# FF.net
KiCad netlist of a schematic drawn in Altium Designer
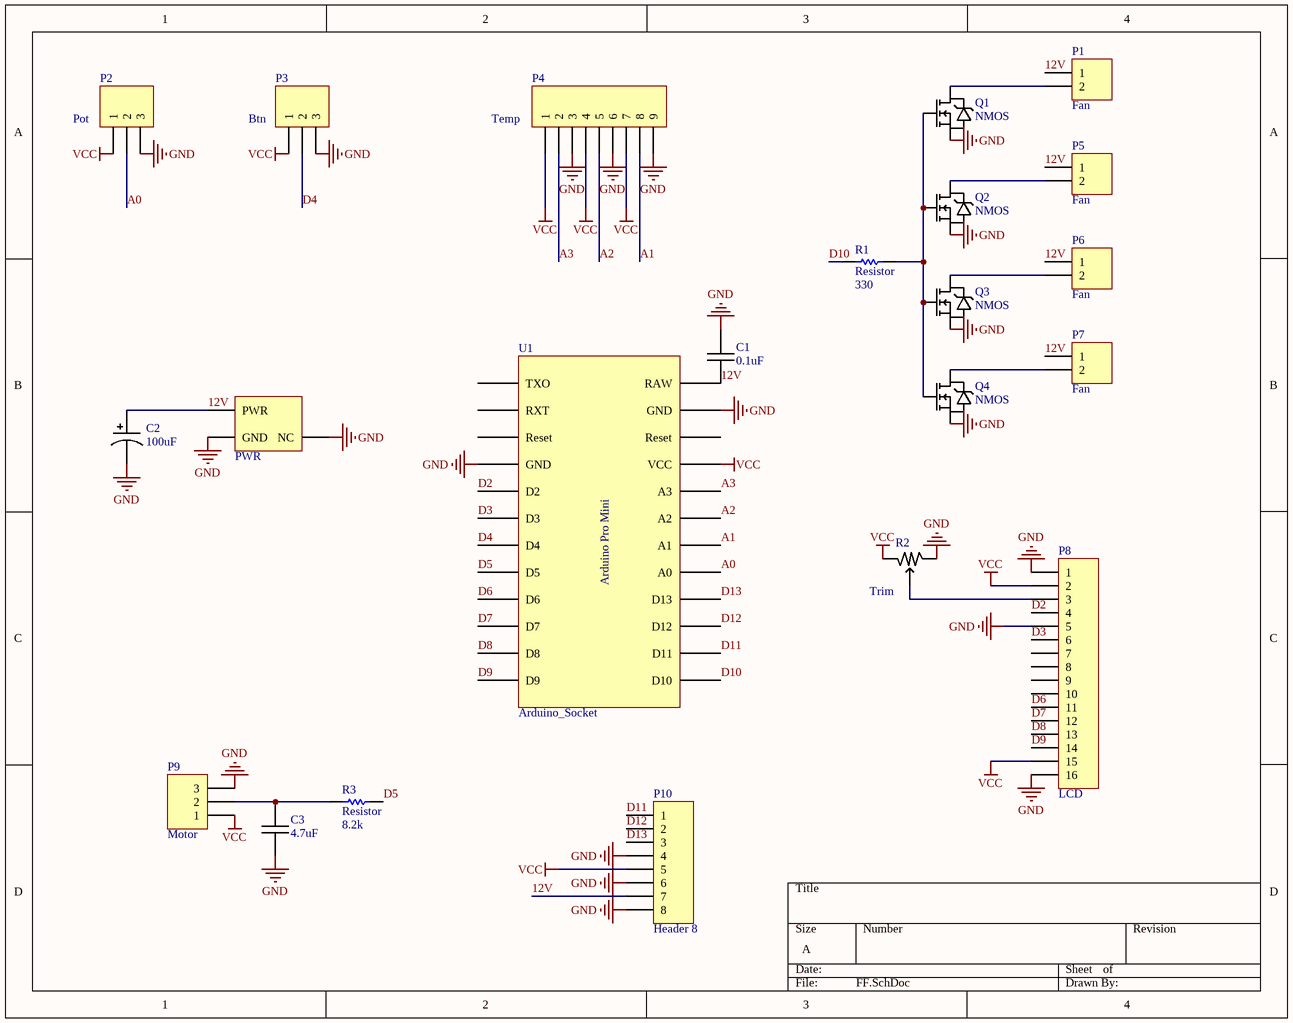
[diagram p0: FF.SchDoc]

(export (version "E")
  (design (tool "Eeschema 10.0.6"))
  (components
    (comp (ref "C1")
      (value "Capacitor")
      (footprint "Cap Axial")
      (description "Ceramic Capacitor")
      (fields (field (name "ALTIUM_UNNAMED_1") "0.1uF"))
      (libsource (lib "Wampler_Devices") (part "Capacitor"))
    )
    (comp (ref "C2")
      (value "Capacitor")
      (footprint "Cap Radial-Can 200")
      (description "Electrolytic Capacitor")
      (fields (field (name "ALTIUM_UNNAMED_1") "100uF"))
      (libsource (lib "Wampler_Devices") (part "Capacitor Polar"))
    )
    (comp (ref "C3")
      (value "Capacitor")
      (footprint "Cap Axial")
      (description "Ceramic Capacitor")
      (fields (field (name "ALTIUM_UNNAMED_1") "4.7uF"))
      (libsource (lib "Wampler_Devices") (part "Capacitor"))
    )
    (comp (ref "P1")
      (value "Fan")
      (footprint "HDR1X2")
      (description "Header, 2-Pin")
      (fields (field (name "PUBLISHER") "Altium Limited"))
      (libsource (lib "Miscellaneous Connectors") (part "Header 2"))
    )
    (comp (ref "P2")
      (value "Pot")
      (footprint "HDR1X3")
      (description "Header, 3-Pin")
      (fields (field (name "PUBLISHER") "Altium Limited"))
      (libsource (lib "") (part "Header 3_1"))
    )
    (comp (ref "P3")
      (value "Btn")
      (footprint "HDR1X3")
      (description "Header, 3-Pin")
      (fields (field (name "PUBLISHER") "Altium Limited"))
      (libsource (lib "") (part "Header 3_1"))
    )
    (comp (ref "P4")
      (value "Temp")
      (footprint "HDR1X9")
      (description "Header, 9-Pin")
      (fields (field (name "PUBLISHER") "Altium Limited"))
      (libsource (lib "Miscellaneous Connectors") (part "Header 9"))
    )
    (comp (ref "P5")
      (value "Fan")
      (footprint "HDR1X2")
      (description "Header, 2-Pin")
      (fields (field (name "PUBLISHER") "Altium Limited"))
      (libsource (lib "Miscellaneous Connectors") (part "Header 2"))
    )
    (comp (ref "P6")
      (value "Fan")
      (footprint "HDR1X2")
      (description "Header, 2-Pin")
      (fields (field (name "PUBLISHER") "Altium Limited"))
      (libsource (lib "Miscellaneous Connectors") (part "Header 2"))
    )
    (comp (ref "P7")
      (value "Fan")
      (footprint "HDR1X2")
      (description "Header, 2-Pin")
      (fields (field (name "PUBLISHER") "Altium Limited"))
      (libsource (lib "Miscellaneous Connectors") (part "Header 2"))
    )
    (comp (ref "P8")
      (value "LCD")
      (footprint "HDR1X16")
      (description "Header, 16-Pin")
      (fields (field (name "PUBLISHER") "Altium Limited"))
      (libsource (lib "Miscellaneous Connectors") (part "Header 16"))
    )
    (comp (ref "P9")
      (value "Motor")
      (footprint "HDR1X3")
      (description "Header, 3-Pin")
      (fields (field (name "PUBLISHER") "Altium Limited"))
      (libsource (lib "Miscellaneous Connectors") (part "Header 3"))
    )
    (comp (ref "P10")
      (value "Header 8")
      (footprint "HDR1X8")
      (description "Header, 8-Pin")
      (fields (field (name "PUBLISHER") "Altium Limited"))
      (libsource (lib "Miscellaneous Connectors") (part "Header 8"))
    )
    (comp (ref "PWR")
      (value "3.5mm Power Jack")
      (footprint "3.5mm Power Jack")
      (libsource (lib "Wampler_Connectors") (part "3.5mm Power Jack"))
    )
    (comp (ref "Q1") (value "NMOS") (footprint "TO-220") (libsource (lib "Wampler_Devices") (part "NMOS")))
    (comp (ref "Q2") (value "NMOS") (footprint "TO-220") (libsource (lib "Wampler_Devices") (part "NMOS")))
    (comp (ref "Q3") (value "NMOS") (footprint "TO-220") (libsource (lib "Wampler_Devices") (part "NMOS")))
    (comp (ref "Q4") (value "NMOS") (footprint "TO-220") (libsource (lib "Wampler_Devices") (part "NMOS")))
    (comp (ref "R1")
      (value "Resistor")
      (footprint "Res Axial 1/2W")
      (fields (field (name "ALTIUM_VALUE") "330") (field (name "PUBLISHER") "Altium Limited"))
      (libsource (lib "Wampler_Devices") (part "Resistor"))
    )
    (comp (ref "R2")
      (value "Trimmer Pot")
      (footprint "T73YP103KT20")
      (fields (field (name "ALTIUM_UNNAMED_1") "Trim"))
      (libsource (lib "Wampler_Devices") (part "Trimmer Pot"))
    )
    (comp (ref "R3")
      (value "Resistor")
      (footprint "Res Axial 1/2W")
      (fields (field (name "ALTIUM_VALUE") "8.2k") (field (name "PUBLISHER") "Altium Limited"))
      (libsource (lib "Wampler_Devices") (part "Resistor"))
    )
    (comp (ref "U1")
      (value "Arduino_Socket")
      (footprint "Arduino_Socket")
      (libsource (lib "Wampler_Devices") (part "Arduino_Socket"))
    )
  )
  (nets
    (net (code "1") (name "/12V") (class "Default")
      (node (ref "C1") (pin "0") (pinfunction "0_0") (pintype "passive"))
      (node (ref "C2") (pin "0") (pinfunction "0_0") (pintype "passive"))
      (node (ref "P1") (pin "1") (pinfunction "1_1") (pintype "passive"))
      (node (ref "P10") (pin "7") (pinfunction "7_7") (pintype "passive"))
      (node (ref "P5") (pin "1") (pinfunction "1_1") (pintype "passive"))
      (node (ref "P6") (pin "1") (pinfunction "1_1") (pintype "passive"))
      (node (ref "P7") (pin "1") (pinfunction "1_1") (pintype "passive"))
      (node (ref "PWR") (pin "1") (pinfunction "PWR_1") (pintype "passive"))
      (node (ref "U1") (pin "24") (pinfunction "RAW_24") (pintype "passive"))
    )
    (net (code "2") (name "/A0") (class "Default")
      (node (ref "P2") (pin "2") (pinfunction "2_2") (pintype "passive"))
      (node (ref "U1") (pin "17") (pinfunction "A0_17") (pintype "passive"))
    )
    (net (code "3") (name "/A1") (class "Default")
      (node (ref "P4") (pin "8") (pinfunction "8_8") (pintype "passive"))
      (node (ref "U1") (pin "18") (pinfunction "A1_18") (pintype "passive"))
    )
    (net (code "4") (name "/A2") (class "Default")
      (node (ref "P4") (pin "5") (pinfunction "5_5") (pintype "passive"))
      (node (ref "U1") (pin "19") (pinfunction "A2_19") (pintype "passive"))
    )
    (net (code "5") (name "/A3") (class "Default")
      (node (ref "P4") (pin "2") (pinfunction "2_2") (pintype "passive"))
      (node (ref "U1") (pin "20") (pinfunction "A3_20") (pintype "passive"))
    )
    (net (code "6") (name "/D2") (class "Default")
      (node (ref "P8") (pin "4") (pinfunction "4_4") (pintype "passive"))
      (node (ref "U1") (pin "5") (pinfunction "D2_5") (pintype "passive"))
    )
    (net (code "7") (name "/D3") (class "Default")
      (node (ref "P8") (pin "6") (pinfunction "6_6") (pintype "passive"))
      (node (ref "U1") (pin "6") (pinfunction "D3_6") (pintype "passive"))
    )
    (net (code "8") (name "/D4") (class "Default")
      (node (ref "P3") (pin "2") (pinfunction "2_2") (pintype "passive"))
      (node (ref "U1") (pin "7") (pinfunction "D4_7") (pintype "passive"))
    )
    (net (code "9") (name "/D5") (class "Default")
      (node (ref "R3") (pin "1") (pinfunction "1_1") (pintype "passive"))
      (node (ref "U1") (pin "8") (pinfunction "D5_8") (pintype "passive"))
    )
    (net (code "10") (name "/D6") (class "Default")
      (node (ref "P8") (pin "11") (pinfunction "11_11") (pintype "passive"))
      (node (ref "U1") (pin "9") (pinfunction "D6_9") (pintype "passive"))
    )
    (net (code "11") (name "/D7") (class "Default")
      (node (ref "P8") (pin "12") (pinfunction "12_12") (pintype "passive"))
      (node (ref "U1") (pin "10") (pinfunction "D7_10") (pintype "passive"))
    )
    (net (code "12") (name "/D8") (class "Default")
      (node (ref "P8") (pin "13") (pinfunction "13_13") (pintype "passive"))
      (node (ref "U1") (pin "11") (pinfunction "D8_11") (pintype "passive"))
    )
    (net (code "13") (name "/D9") (class "Default")
      (node (ref "P8") (pin "14") (pinfunction "14_14") (pintype "passive"))
      (node (ref "U1") (pin "12") (pinfunction "D9_12") (pintype "passive"))
    )
    (net (code "14") (name "/D10") (class "Default")
      (node (ref "R1") (pin "1") (pinfunction "1_1") (pintype "passive"))
      (node (ref "U1") (pin "13") (pinfunction "D10_13") (pintype "passive"))
    )
    (net (code "15") (name "/D11") (class "Default")
      (node (ref "P10") (pin "1") (pinfunction "1_1") (pintype "passive"))
      (node (ref "U1") (pin "14") (pinfunction "D11_14") (pintype "passive"))
    )
    (net (code "16") (name "/D12") (class "Default")
      (node (ref "P10") (pin "2") (pinfunction "2_2") (pintype "passive"))
      (node (ref "U1") (pin "15") (pinfunction "D12_15") (pintype "passive"))
    )
    (net (code "17") (name "/D13") (class "Default")
      (node (ref "P10") (pin "3") (pinfunction "3_3") (pintype "passive"))
      (node (ref "U1") (pin "16") (pinfunction "D13_16") (pintype "passive"))
    )
    (net (code "18") (name "GND") (class "Default")
      (node (ref "C1") (pin "1") (pinfunction "1_1") (pintype "passive"))
      (node (ref "C2") (pin "1") (pinfunction "1_1") (pintype "passive"))
      (node (ref "C3") (pin "0") (pinfunction "0_0") (pintype "passive"))
      (node (ref "P10") (pin "4") (pinfunction "4_4") (pintype "passive"))
      (node (ref "P10") (pin "6") (pinfunction "6_6") (pintype "passive"))
      (node (ref "P10") (pin "8") (pinfunction "8_8") (pintype "passive"))
      (node (ref "P2") (pin "3") (pinfunction "3_3") (pintype "passive"))
      (node (ref "P3") (pin "3") (pinfunction "3_3") (pintype "passive"))
      (node (ref "P4") (pin "3") (pinfunction "3_3") (pintype "passive"))
      (node (ref "P4") (pin "6") (pinfunction "6_6") (pintype "passive"))
      (node (ref "P4") (pin "9") (pinfunction "9_9") (pintype "passive"))
      (node (ref "P8") (pin "1") (pinfunction "1_1") (pintype "passive"))
      (node (ref "P8") (pin "16") (pinfunction "16_16") (pintype "passive"))
      (node (ref "P8") (pin "5") (pinfunction "5_5") (pintype "passive"))
      (node (ref "P9") (pin "3") (pinfunction "3_3") (pintype "passive"))
      (node (ref "PWR") (pin "2") (pinfunction "GND_2") (pintype "passive"))
      (node (ref "PWR") (pin "3") (pinfunction "NC_3") (pintype "passive"))
      (node (ref "Q1") (pin "3") (pinfunction "3_3") (pintype "passive"))
      (node (ref "Q2") (pin "3") (pinfunction "3_3") (pintype "passive"))
      (node (ref "Q3") (pin "3") (pinfunction "3_3") (pintype "passive"))
      (node (ref "Q4") (pin "3") (pinfunction "3_3") (pintype "passive"))
      (node (ref "R2") (pin "1") (pinfunction "1_1") (pintype "passive"))
      (node (ref "U1") (pin "23") (pinfunction "GND_23") (pintype "passive"))
      (node (ref "U1") (pin "4") (pinfunction "GND_4") (pintype "passive"))
    )
    (net (code "19") (name "Net-(C3-Pad1)") (class "Default")
      (node (ref "C3") (pin "1") (pinfunction "1_1") (pintype "passive"))
      (node (ref "P9") (pin "2") (pinfunction "2_2") (pintype "passive"))
      (node (ref "R3") (pin "2") (pinfunction "2_2") (pintype "passive"))
    )
    (net (code "20") (name "Net-(P1-Pad2)") (class "Default")
      (node (ref "P1") (pin "2") (pinfunction "2_2") (pintype "passive"))
      (node (ref "Q1") (pin "2") (pinfunction "2_2") (pintype "passive"))
    )
    (net (code "21") (name "Net-(P5-Pad2)") (class "Default")
      (node (ref "P5") (pin "2") (pinfunction "2_2") (pintype "passive"))
      (node (ref "Q2") (pin "2") (pinfunction "2_2") (pintype "passive"))
    )
    (net (code "22") (name "Net-(P6-Pad2)") (class "Default")
      (node (ref "P6") (pin "2") (pinfunction "2_2") (pintype "passive"))
      (node (ref "Q3") (pin "2") (pinfunction "2_2") (pintype "passive"))
    )
    (net (code "23") (name "Net-(P7-Pad2)") (class "Default")
      (node (ref "P7") (pin "2") (pinfunction "2_2") (pintype "passive"))
      (node (ref "Q4") (pin "2") (pinfunction "2_2") (pintype "passive"))
    )
    (net (code "24") (name "Net-(P8-Pad3)") (class "Default")
      (node (ref "P8") (pin "3") (pinfunction "3_3") (pintype "passive"))
      (node (ref "R2") (pin "2") (pinfunction "2_2") (pintype "passive"))
    )
    (net (code "25") (name "Net-(Q1-Pad1)") (class "Default")
      (node (ref "Q1") (pin "1") (pinfunction "1_1") (pintype "passive"))
      (node (ref "Q2") (pin "1") (pinfunction "1_1") (pintype "passive"))
      (node (ref "Q3") (pin "1") (pinfunction "1_1") (pintype "passive"))
      (node (ref "Q4") (pin "1") (pinfunction "1_1") (pintype "passive"))
      (node (ref "R1") (pin "2") (pinfunction "2_2") (pintype "passive"))
    )
    (net (code "26") (name "VCC") (class "Default")
      (node (ref "P10") (pin "5") (pinfunction "5_5") (pintype "passive"))
      (node (ref "P2") (pin "1") (pinfunction "1_1") (pintype "passive"))
      (node (ref "P3") (pin "1") (pinfunction "1_1") (pintype "passive"))
      (node (ref "P4") (pin "1") (pinfunction "1_1") (pintype "passive"))
      (node (ref "P4") (pin "4") (pinfunction "4_4") (pintype "passive"))
      (node (ref "P4") (pin "7") (pinfunction "7_7") (pintype "passive"))
      (node (ref "P8") (pin "15") (pinfunction "15_15") (pintype "passive"))
      (node (ref "P8") (pin "2") (pinfunction "2_2") (pintype "passive"))
      (node (ref "P9") (pin "1") (pinfunction "1_1") (pintype "passive"))
      (node (ref "R2") (pin "0") (pinfunction "0_0") (pintype "passive"))
      (node (ref "U1") (pin "21") (pinfunction "VCC_21") (pintype "passive"))
    )
    (net (code "27") (name "unconnected-(P8-Pad7)") (class "Default")
      (node (ref "P8") (pin "7") (pinfunction "7_7") (pintype "passive"))
    )
    (net (code "28") (name "unconnected-(P8-Pad8)") (class "Default")
      (node (ref "P8") (pin "8") (pinfunction "8_8") (pintype "passive"))
    )
    (net (code "29") (name "unconnected-(P8-Pad9)") (class "Default")
      (node (ref "P8") (pin "9") (pinfunction "9_9") (pintype "passive"))
    )
    (net (code "30") (name "unconnected-(P8-Pad10)") (class "Default")
      (node (ref "P8") (pin "10") (pinfunction "10_10") (pintype "passive"))
    )
    (net (code "31") (name "unconnected-(U1-RXT-Pad2)") (class "Default")
      (node (ref "U1") (pin "2") (pinfunction "RXT_2") (pintype "passive"))
    )
    (net (code "32") (name "unconnected-(U1-Reset-Pad3)") (class "Default")
      (node (ref "U1") (pin "3") (pinfunction "Reset_3") (pintype "passive"))
    )
    (net (code "33") (name "unconnected-(U1-Reset-Pad22)") (class "Default")
      (node (ref "U1") (pin "22") (pinfunction "Reset_22") (pintype "passive"))
    )
    (net (code "34") (name "unconnected-(U1-TXO-Pad1)") (class "Default")
      (node (ref "U1") (pin "1") (pinfunction "TXO_1") (pintype "passive"))
    )
  )
)
